# RoomSensor.net
KiCad netlist of a schematic drawn in EAGLE
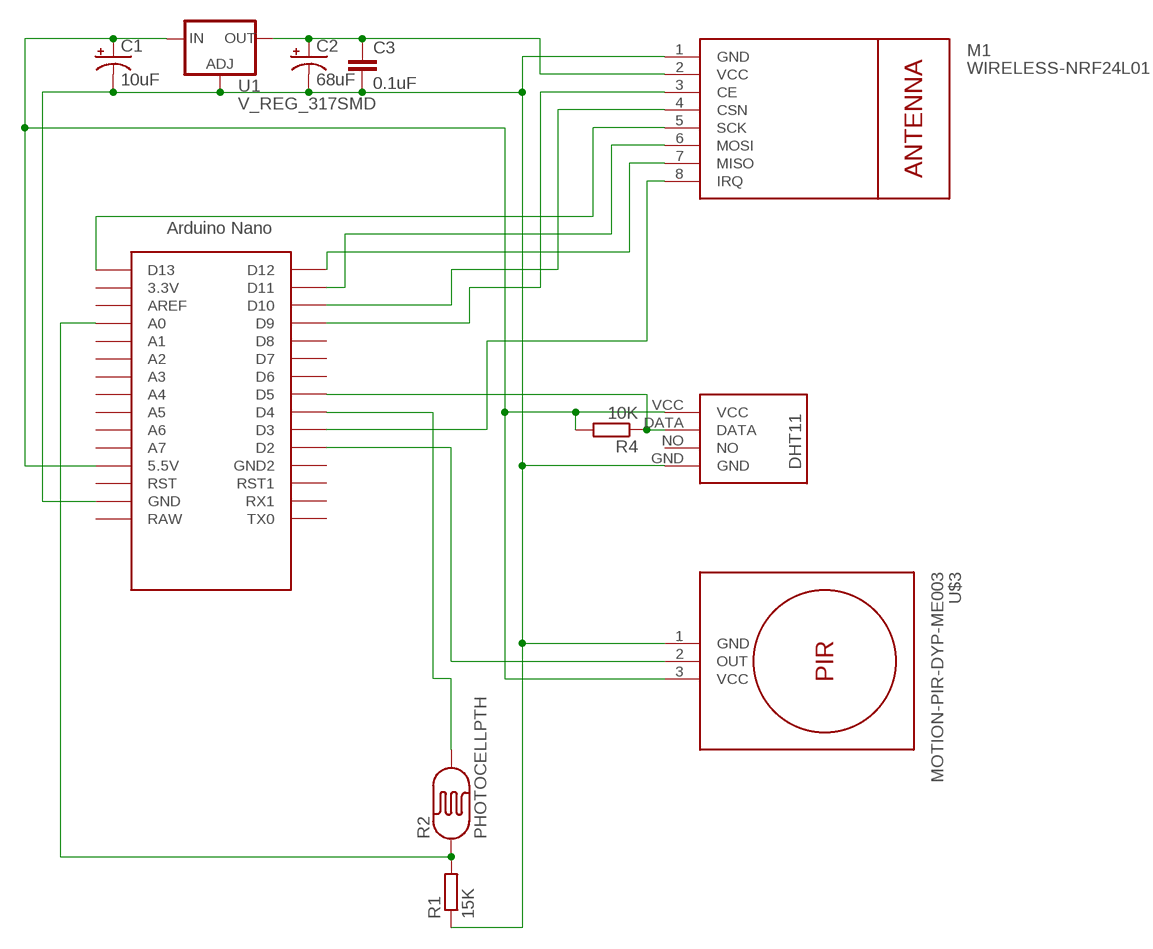
[diagram p0: schematic, sheet 1]

(export (version "E")
  (design (tool "Eeschema 10.0.6"))
  (components
    (comp (ref "C1")
      (value "10uF")
      (footprint "eagle-import:EIA3216")
      (libsource (lib "eagle-import") (part "CAP_POL1206"))
    )
    (comp (ref "C2")
      (value "68uF")
      (footprint "eagle-import:EIA3216")
      (libsource (lib "eagle-import") (part "CAP_POL1206"))
    )
    (comp (ref "C3")
      (value "0.1uF")
      (footprint "eagle-import:0603-CAP")
      (libsource (lib "eagle-import") (part "CAP0603-CAP"))
    )
    (comp (ref "M1")
      (value "WIRELESS-NRF24L01")
      (footprint "eagle-import:WIRELESS-NRF24L01")
      (libsource (lib "eagle-import") (part "WIRELESS-NRF24L01"))
    )
    (comp (ref "R1")
      (value "15K")
      (footprint "eagle-import:0204V")
      (libsource (lib "eagle-import") (part "R-EU_0204/2V"))
    )
    (comp (ref "R2")
      (value "PHOTOCELLPTH")
      (footprint "eagle-import:PHOTOCELL")
      (libsource (lib "eagle-import") (part "PHOTOCELLPTH"))
    )
    (comp (ref "R4")
      (value "10K")
      (footprint "eagle-import:0204V")
      (libsource (lib "eagle-import") (part "R-EU_0204/2V"))
    )
    (comp (ref "U$1")
      (value "NANO")
      (footprint "eagle-import:NANO")
      (libsource (lib "eagle-import") (part "NANO"))
    )
    (comp (ref "U$2")
      (value "DHT11")
      (footprint "eagle-import:DHT11")
      (libsource (lib "eagle-import") (part "DHT11"))
    )
    (comp (ref "U$3")
      (value "MOTION-PIR-DYP-ME003")
      (footprint "eagle-import:MOTION-PIR-DYP-ME003")
      (libsource (lib "eagle-import") (part "MOTION-PIR-DYP-ME003"))
    )
    (comp (ref "U1")
      (value "V_REG_317SMD")
      (footprint "eagle-import:SOT223")
      (libsource (lib "eagle-import") (part "V_REG_317SMD"))
    )
  )
  (nets
    (net (code "1") (name "Net-(C1-+)") (class "Default")
      (node (ref "C1") (pin "A") (pinfunction "+_A") (pintype "passive"))
      (node (ref "R4") (pin "2") (pinfunction "2_2") (pintype "passive"))
      (node (ref "U$1") (pin "5V") (pinfunction "5.5V_5V") (pintype "bidirectional"))
      (node (ref "U$2") (pin "VCC") (pinfunction "VCC_VCC") (pintype "bidirectional"))
      (node (ref "U$3") (pin "3") (pinfunction "VCC_3") (pintype "power_in"))
      (node (ref "U1") (pin "3") (pinfunction "IN_3") (pintype "input"))
    )
    (net (code "2") (name "Net-(C1--)") (class "Default")
      (node (ref "C1") (pin "C") (pinfunction "-_C") (pintype "passive"))
      (node (ref "C2") (pin "C") (pinfunction "-_C") (pintype "passive"))
      (node (ref "C3") (pin "2") (pinfunction "2_2") (pintype "passive"))
      (node (ref "M1") (pin "1") (pinfunction "GND_1") (pintype "power_in"))
      (node (ref "R1") (pin "1") (pinfunction "1_1") (pintype "passive"))
      (node (ref "U$1") (pin "GND") (pinfunction "GND_GND") (pintype "bidirectional"))
      (node (ref "U$2") (pin "GND") (pinfunction "GND_GND") (pintype "bidirectional"))
      (node (ref "U$3") (pin "1") (pinfunction "GND_1") (pintype "power_in"))
      (node (ref "U1") (pin "1") (pinfunction "ADJ_1") (pintype "input"))
    )
    (net (code "3") (name "Net-(C2-+)") (class "Default")
      (node (ref "C2") (pin "A") (pinfunction "+_A") (pintype "passive"))
      (node (ref "C3") (pin "1") (pinfunction "1_1") (pintype "passive"))
      (node (ref "M1") (pin "2") (pinfunction "VCC_2") (pintype "power_in"))
      (node (ref "U1") (pin "2") (pinfunction "OUT_2") (pintype "output"))
    )
    (net (code "4") (name "Net-(M1-CE)") (class "Default")
      (node (ref "M1") (pin "3") (pinfunction "CE_3") (pintype "bidirectional"))
      (node (ref "U$1") (pin "D9") (pinfunction "D9_D9") (pintype "bidirectional"))
    )
    (net (code "5") (name "Net-(M1-CSN)") (class "Default")
      (node (ref "M1") (pin "4") (pinfunction "CSN_4") (pintype "bidirectional"))
      (node (ref "U$1") (pin "D10") (pinfunction "D10_D10") (pintype "bidirectional"))
    )
    (net (code "6") (name "Net-(M1-IRQ)") (class "Default")
      (node (ref "M1") (pin "8") (pinfunction "IRQ_8") (pintype "bidirectional"))
      (node (ref "U$1") (pin "D3") (pinfunction "D3_D3") (pintype "bidirectional"))
    )
    (net (code "7") (name "Net-(M1-MISO)") (class "Default")
      (node (ref "M1") (pin "7") (pinfunction "MISO_7") (pintype "bidirectional"))
      (node (ref "U$1") (pin "D12") (pinfunction "D12_D12") (pintype "bidirectional"))
    )
    (net (code "8") (name "Net-(M1-MOSI)") (class "Default")
      (node (ref "M1") (pin "6") (pinfunction "MOSI_6") (pintype "bidirectional"))
      (node (ref "U$1") (pin "D11") (pinfunction "D11_D11") (pintype "bidirectional"))
    )
    (net (code "9") (name "Net-(M1-SCK)") (class "Default")
      (node (ref "M1") (pin "5") (pinfunction "SCK_5") (pintype "bidirectional"))
      (node (ref "U$1") (pin "D13") (pinfunction "D13_D13") (pintype "bidirectional"))
    )
    (net (code "10") (name "Net-(R2-P$1)") (class "Default")
      (node (ref "R1") (pin "2") (pinfunction "2_2") (pintype "passive"))
      (node (ref "R2") (pin "1") (pinfunction "P$1_1") (pintype "bidirectional"))
      (node (ref "U$1") (pin "A0") (pinfunction "A0_A0") (pintype "bidirectional"))
    )
    (net (code "11") (name "Net-(R2-P$2)") (class "Default")
      (node (ref "R2") (pin "2") (pinfunction "P$2_2") (pintype "bidirectional"))
      (node (ref "U$1") (pin "D4") (pinfunction "D4_D4") (pintype "bidirectional"))
    )
    (net (code "12") (name "Net-(R4-Pad1)") (class "Default")
      (node (ref "R4") (pin "1") (pinfunction "1_1") (pintype "passive"))
      (node (ref "U$1") (pin "D5") (pinfunction "D5_D5") (pintype "bidirectional"))
      (node (ref "U$2") (pin "DATA") (pinfunction "DATA_DATA") (pintype "bidirectional"))
    )
    (net (code "13") (name "Net-(U$3-OUT)") (class "Default")
      (node (ref "U$1") (pin "D2") (pinfunction "D2_D2") (pintype "bidirectional"))
      (node (ref "U$3") (pin "2") (pinfunction "OUT_2") (pintype "output"))
    )
    (net (code "14") (name "unconnected-(U$1-GND2-PadGND1)") (class "Default")
      (node (ref "U$1") (pin "GND1") (pinfunction "GND2_GND1") (pintype "bidirectional"))
    )
    (net (code "15") (name "unconnected-(U$1-Pad3.3V)") (class "Default")
      (node (ref "U$1") (pin "3.3V") (pinfunction "3.3V_3.3V") (pintype "bidirectional"))
    )
    (net (code "16") (name "unconnected-(U$1-PadA1)") (class "Default")
      (node (ref "U$1") (pin "A1") (pinfunction "A1_A1") (pintype "bidirectional"))
    )
    (net (code "17") (name "unconnected-(U$1-PadA2)") (class "Default")
      (node (ref "U$1") (pin "A2") (pinfunction "A2_A2") (pintype "bidirectional"))
    )
    (net (code "18") (name "unconnected-(U$1-PadA3)") (class "Default")
      (node (ref "U$1") (pin "A3") (pinfunction "A3_A3") (pintype "bidirectional"))
    )
    (net (code "19") (name "unconnected-(U$1-PadA4)") (class "Default")
      (node (ref "U$1") (pin "A4") (pinfunction "A4_A4") (pintype "bidirectional"))
    )
    (net (code "20") (name "unconnected-(U$1-PadA5)") (class "Default")
      (node (ref "U$1") (pin "A5") (pinfunction "A5_A5") (pintype "bidirectional"))
    )
    (net (code "21") (name "unconnected-(U$1-PadA6)") (class "Default")
      (node (ref "U$1") (pin "A6") (pinfunction "A6_A6") (pintype "bidirectional"))
    )
    (net (code "22") (name "unconnected-(U$1-PadA7)") (class "Default")
      (node (ref "U$1") (pin "A7") (pinfunction "A7_A7") (pintype "bidirectional"))
    )
    (net (code "23") (name "unconnected-(U$1-PadAREF)") (class "Default")
      (node (ref "U$1") (pin "AREF") (pinfunction "AREF_AREF") (pintype "bidirectional"))
    )
    (net (code "24") (name "unconnected-(U$1-PadD6)") (class "Default")
      (node (ref "U$1") (pin "D6") (pinfunction "D6_D6") (pintype "bidirectional"))
    )
    (net (code "25") (name "unconnected-(U$1-PadD7)") (class "Default")
      (node (ref "U$1") (pin "D7") (pinfunction "D7_D7") (pintype "bidirectional"))
    )
    (net (code "26") (name "unconnected-(U$1-PadD8)") (class "Default")
      (node (ref "U$1") (pin "D8") (pinfunction "D8_D8") (pintype "bidirectional"))
    )
    (net (code "27") (name "unconnected-(U$1-PadICSP1)") (class "Default")
      (node (ref "U$1") (pin "ICSP1") (pinfunction "ICSP1_ICSP1") (pintype "bidirectional"))
    )
    (net (code "28") (name "unconnected-(U$1-PadICSP2)") (class "Default")
      (node (ref "U$1") (pin "ICSP2") (pinfunction "ICSP2_ICSP2") (pintype "bidirectional"))
    )
    (net (code "29") (name "unconnected-(U$1-PadICSP3)") (class "Default")
      (node (ref "U$1") (pin "ICSP3") (pinfunction "ICSP3_ICSP3") (pintype "bidirectional"))
    )
    (net (code "30") (name "unconnected-(U$1-PadICSP4)") (class "Default")
      (node (ref "U$1") (pin "ICSP4") (pinfunction "ICSP4_ICSP4") (pintype "bidirectional"))
    )
    (net (code "31") (name "unconnected-(U$1-PadICSP5)") (class "Default")
      (node (ref "U$1") (pin "ICSP5") (pinfunction "ICSP5_ICSP5") (pintype "bidirectional"))
    )
    (net (code "32") (name "unconnected-(U$1-PadICSP6)") (class "Default")
      (node (ref "U$1") (pin "ICSP6") (pinfunction "ICSP6_ICSP6") (pintype "bidirectional"))
    )
    (net (code "33") (name "unconnected-(U$1-PadRAW)") (class "Default")
      (node (ref "U$1") (pin "RAW") (pinfunction "RAW_RAW") (pintype "bidirectional"))
    )
    (net (code "34") (name "unconnected-(U$1-PadRST)") (class "Default")
      (node (ref "U$1") (pin "RST") (pinfunction "RST_RST") (pintype "bidirectional"))
    )
    (net (code "35") (name "unconnected-(U$1-PadRST1)") (class "Default")
      (node (ref "U$1") (pin "RST1") (pinfunction "RST1_RST1") (pintype "bidirectional"))
    )
    (net (code "36") (name "unconnected-(U$1-PadRX1)") (class "Default")
      (node (ref "U$1") (pin "RX1") (pinfunction "RX1_RX1") (pintype "bidirectional"))
    )
    (net (code "37") (name "unconnected-(U$1-PadTX0)") (class "Default")
      (node (ref "U$1") (pin "TX0") (pinfunction "TX0_TX0") (pintype "bidirectional"))
    )
    (net (code "38") (name "unconnected-(U$2-PadNO)") (class "Default")
      (node (ref "U$2") (pin "NO") (pinfunction "NO_NO") (pintype "bidirectional"))
    )
  )
)
